# main.net
KiCad netlist of a schematic drawn in EAGLE
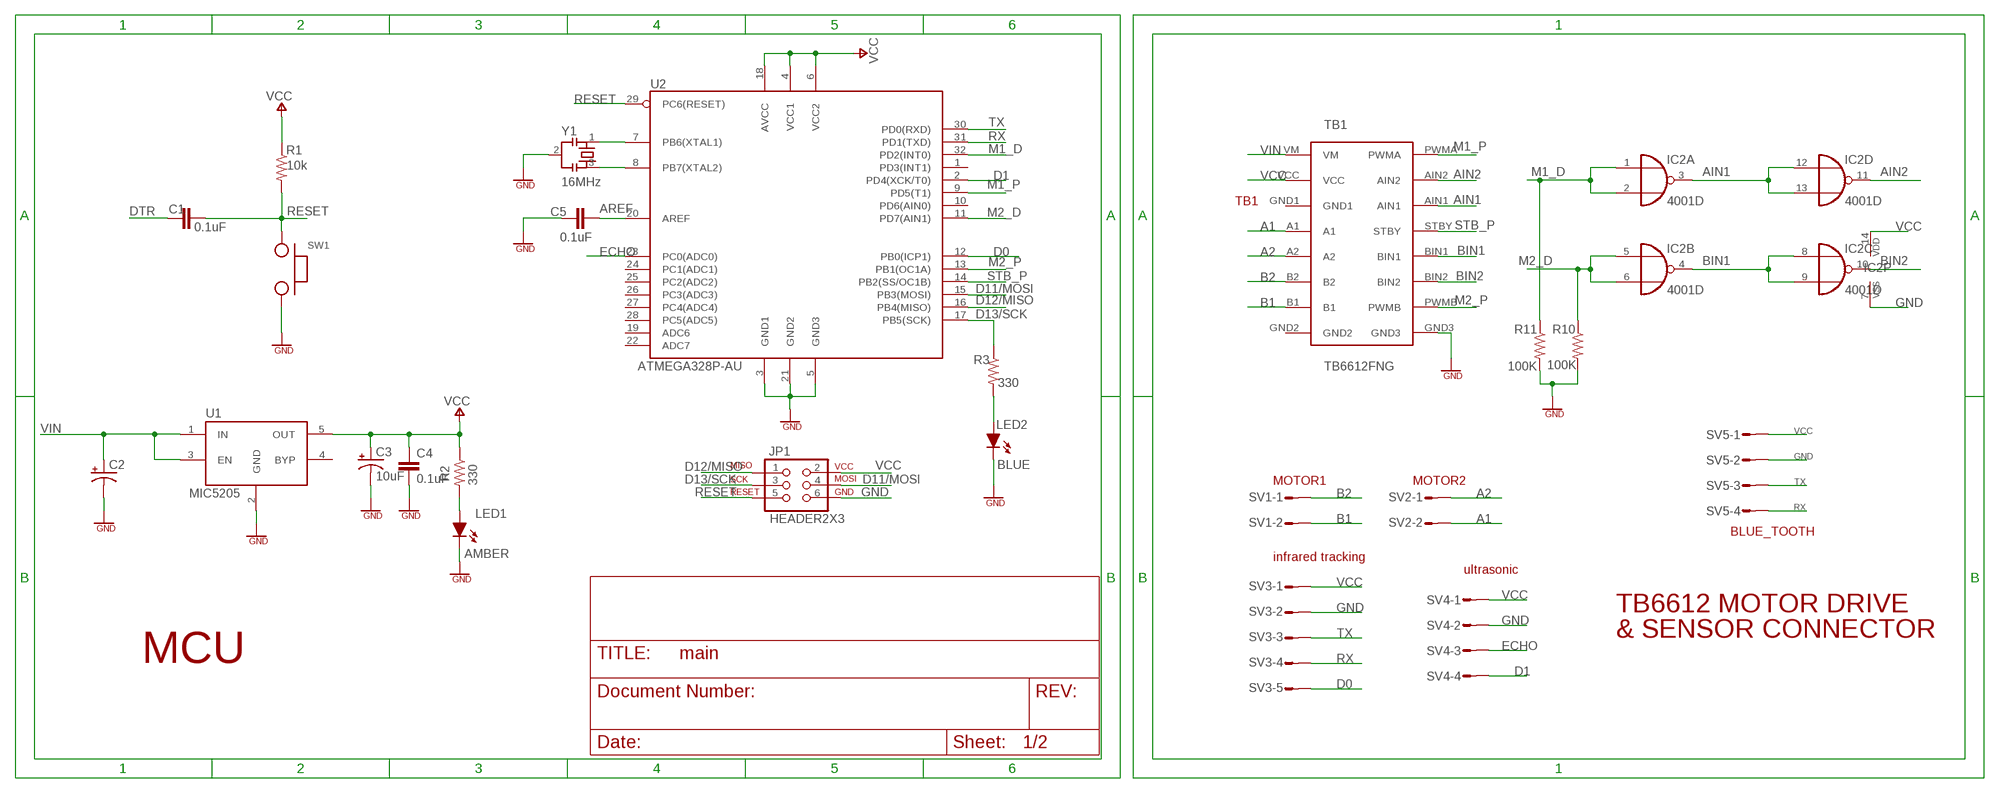
[diagram p0: schematic, sheet 1]
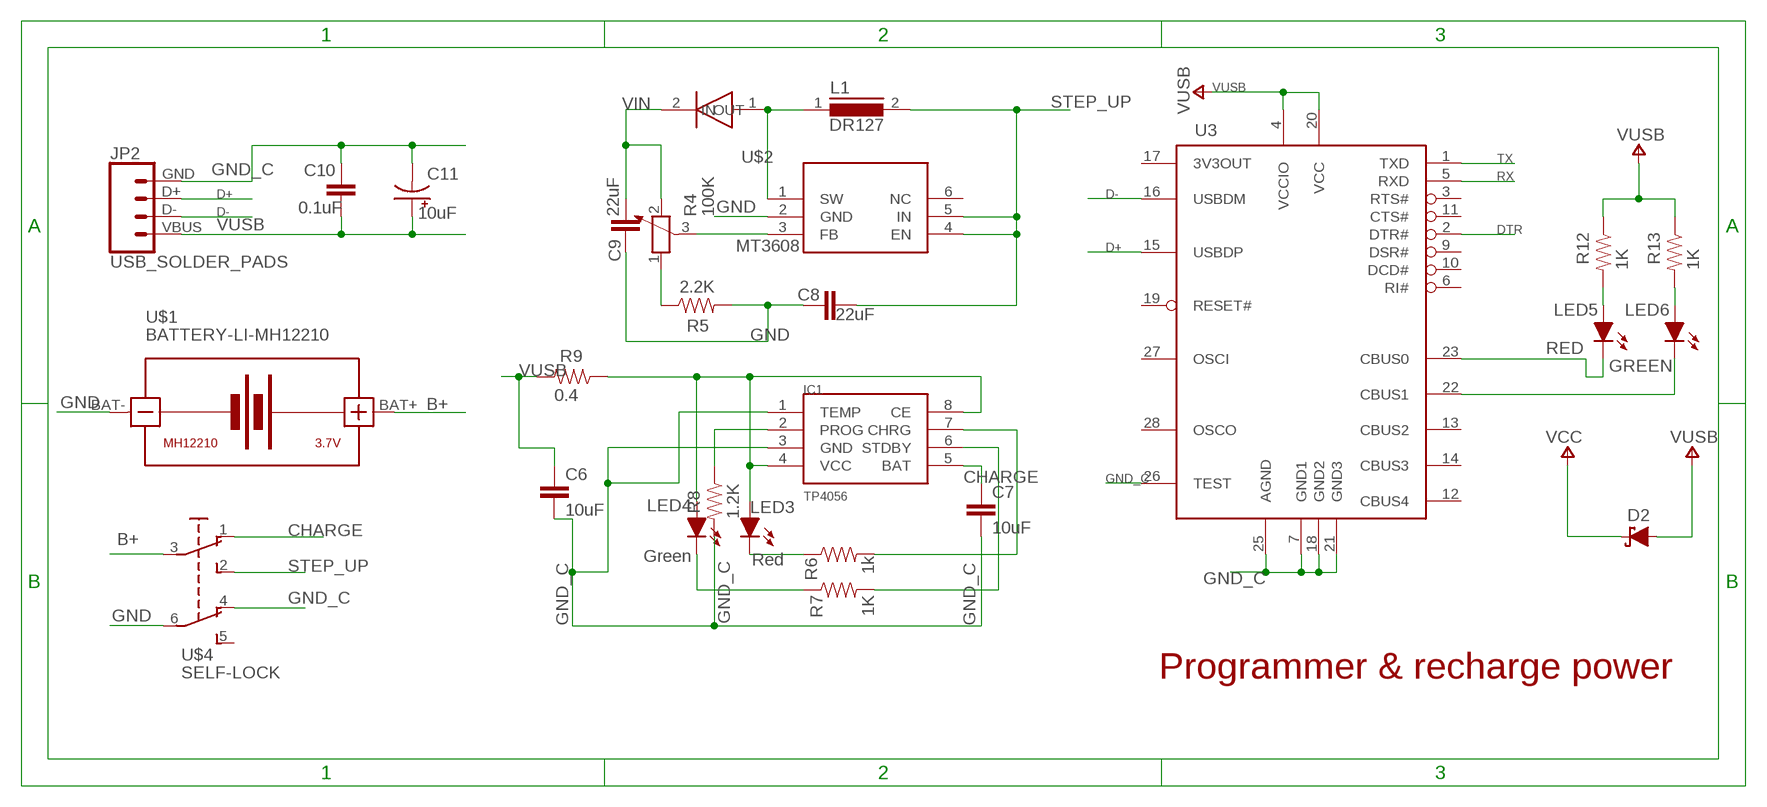
[diagram p1: schematic, sheet 2]

(export (version "E")
  (design (tool "Eeschema 10.0.6"))
  (components
    (comp (ref "C1")
      (value "0.1uF")
      (footprint "eagle-import:SMD0603")
      (libsource (lib "eagle-import") (part "CAP_0603"))
    )
    (comp (ref "C2")
      (value "CAP_TANT")
      (footprint "eagle-import:EIA3216")
      (libsource (lib "eagle-import") (part "CAP_TANT"))
    )
    (comp (ref "C3")
      (value "10uF")
      (footprint "eagle-import:EIA3216")
      (libsource (lib "eagle-import") (part "CAP_TANT"))
    )
    (comp (ref "C4")
      (value "0.1uF")
      (footprint "eagle-import:SMD0603")
      (libsource (lib "eagle-import") (part "CAP_0603"))
    )
    (comp (ref "C5")
      (value "0.1uF")
      (footprint "eagle-import:SMD0603")
      (libsource (lib "eagle-import") (part "CAP_0603"))
    )
    (comp (ref "IC2")
      (value "4001D")
      (footprint "eagle-import:SO14")
      (libsource (lib "eagle-import") (part "4001D"))
    )
    (comp (ref "JP1")
      (value "HEADER2X3")
      (footprint "eagle-import:2X3")
      (libsource (lib "eagle-import") (part "HEADER2X3"))
    )
    (comp (ref "LED1")
      (value "AMBER")
      (footprint "eagle-import:LED_0603")
      (libsource (lib "eagle-import") (part "LED_0603"))
    )
    (comp (ref "LED2")
      (value "BLUE")
      (footprint "eagle-import:LED_0805")
      (libsource (lib "eagle-import") (part "LED_0805"))
    )
    (comp (ref "R1")
      (value "10k")
      (footprint "eagle-import:SMD0603")
      (libsource (lib "eagle-import") (part "RES_0603"))
    )
    (comp (ref "R2")
      (value "330")
      (footprint "eagle-import:SMD0603")
      (libsource (lib "eagle-import") (part "RES_0603"))
    )
    (comp (ref "R3")
      (value "330")
      (footprint "eagle-import:SMD0603")
      (libsource (lib "eagle-import") (part "RES_0603"))
    )
    (comp (ref "R10")
      (value "100K")
      (footprint "eagle-import:SMD0603")
      (libsource (lib "eagle-import") (part "RES_0603"))
    )
    (comp (ref "R11")
      (value "100K")
      (footprint "eagle-import:SMD0603")
      (libsource (lib "eagle-import") (part "RES_0603"))
    )
    (comp (ref "SV1")
      (value "L02P")
      (footprint "eagle-import:L02P")
      (libsource (lib "eagle-import") (part "L02P"))
    )
    (comp (ref "SV2")
      (value "L02P")
      (footprint "eagle-import:L02P")
      (libsource (lib "eagle-import") (part "L02P"))
    )
    (comp (ref "SV3")
      (value "L05P")
      (footprint "eagle-import:L05P")
      (libsource (lib "eagle-import") (part "L05P"))
    )
    (comp (ref "SV4")
      (value "MT6-4")
      (footprint "eagle-import:MT6-4")
      (libsource (lib "eagle-import") (part "MT6-4"))
    )
    (comp (ref "SV5")
      (value "MT6-4")
      (footprint "eagle-import:MT6-4")
      (libsource (lib "eagle-import") (part "MT6-4"))
    )
    (comp (ref "SW1")
      (value "SWITCH")
      (footprint "eagle-import:SWITCH-SPST")
      (libsource (lib "eagle-import") (part "SWITCH"))
    )
    (comp (ref "TB1")
      (value "TB6612FNG")
      (footprint "eagle-import:TB6612FNG")
      (libsource (lib "eagle-import") (part "TB6612FNG"))
    )
    (comp (ref "U1")
      (value "MIC5205")
      (footprint "eagle-import:SOT23-5")
      (libsource (lib "eagle-import") (part "MIC5205"))
    )
    (comp (ref "U2")
      (value "ATMEGA328P-AU")
      (footprint "eagle-import:TQFP32")
      (libsource (lib "eagle-import") (part "ATMEGA328P-AU"))
    )
    (comp (ref "Y1")
      (value "16MHz")
      (footprint "eagle-import:CSTCE")
      (libsource (lib "eagle-import") (part "CSTCE"))
    )
    (comp (ref "C6")
      (value "10uF")
      (footprint "eagle-import:SMD0805")
      (libsource (lib "eagle-import") (part "CAP_0805"))
    )
    (comp (ref "C7")
      (value "10uF")
      (footprint "eagle-import:SMD0805")
      (libsource (lib "eagle-import") (part "CAP_0805"))
    )
    (comp (ref "C8")
      (value "22uF")
      (footprint "eagle-import:SMD0805")
      (libsource (lib "eagle-import") (part "CAP_0805"))
    )
    (comp (ref "C9")
      (value "22uF")
      (footprint "eagle-import:SMD0805")
      (libsource (lib "eagle-import") (part "CAP_0805"))
    )
    (comp (ref "C10")
      (value "0.1uF")
      (footprint "eagle-import:SMD0603")
      (libsource (lib "eagle-import") (part "CAP_0603"))
    )
    (comp (ref "C11")
      (value "10uF")
      (footprint "eagle-import:EIA3216")
      (libsource (lib "eagle-import") (part "CAP_TANT"))
    )
    (comp (ref "D2")
      (value "SCHOTTKY")
      (footprint "eagle-import:SOD123")
      (libsource (lib "eagle-import") (part "SCHOTTKY"))
    )
    (comp (ref "IC1")
      (value "TP4056")
      (footprint "eagle-import:SOP-8")
      (libsource (lib "eagle-import") (part "TP4056"))
    )
    (comp (ref "JP2")
      (value "USB_SOLDER_PADS")
      (footprint "eagle-import:USB-SOLDER-PADS")
      (libsource (lib "eagle-import") (part "USB_SOLDER_PADS"))
    )
    (comp (ref "L1")
      (value "DR127")
      (footprint "eagle-import:DR127")
      (libsource (lib "eagle-import") (part "DR127"))
    )
    (comp (ref "LED3")
      (value "Red")
      (footprint "eagle-import:LED_0603")
      (libsource (lib "eagle-import") (part "LED_0603"))
    )
    (comp (ref "LED4")
      (value "Green")
      (footprint "eagle-import:LED_0603")
      (libsource (lib "eagle-import") (part "LED_0603"))
    )
    (comp (ref "LED5")
      (value "RED")
      (footprint "eagle-import:LED_0603")
      (libsource (lib "eagle-import") (part "LED_0603"))
    )
    (comp (ref "LED6")
      (value "GREEN")
      (footprint "eagle-import:LED_0603")
      (libsource (lib "eagle-import") (part "LED_0603"))
    )
    (comp (ref "R4")
      (value "100K")
      (footprint "eagle-import:PT-10")
      (libsource (lib "eagle-import") (part "POTENTIOMETER_PT-10"))
    )
    (comp (ref "R5")
      (value "2.2K")
      (footprint "eagle-import:SMD0603")
      (libsource (lib "eagle-import") (part "RES_0603"))
    )
    (comp (ref "R6")
      (value "1k")
      (footprint "eagle-import:SMD0603")
      (libsource (lib "eagle-import") (part "RES_0603"))
    )
    (comp (ref "R7")
      (value "1K")
      (footprint "eagle-import:SMD0603")
      (libsource (lib "eagle-import") (part "RES_0603"))
    )
    (comp (ref "R8")
      (value "1.2K")
      (footprint "eagle-import:SMD0603")
      (libsource (lib "eagle-import") (part "RES_0603"))
    )
    (comp (ref "R9")
      (value "0.4")
      (footprint "eagle-import:SMD0805")
      (libsource (lib "eagle-import") (part "RES_0805"))
    )
    (comp (ref "R12")
      (value "1K")
      (footprint "eagle-import:SMD0603")
      (libsource (lib "eagle-import") (part "RES_0603"))
    )
    (comp (ref "R13")
      (value "1K")
      (footprint "eagle-import:SMD0603")
      (libsource (lib "eagle-import") (part "RES_0603"))
    )
    (comp (ref "U$1")
      (value "BATTERY-LI-MH12210")
      (footprint "eagle-import:BATTERY-LI-MH12210")
      (libsource (lib "eagle-import") (part "BATTERY-LI-MH12210"))
    )
    (comp (ref "U$2")
      (value "MT3608")
      (footprint "eagle-import:SOT23-6")
      (libsource (lib "eagle-import") (part "MT3608"))
    )
    (comp (ref "U$3")
      (value "SMA-SS34")
      (footprint "eagle-import:SMA-SS34")
      (libsource (lib "eagle-import") (part "SMA-SS34"))
    )
    (comp (ref "U$4")
      (value "SELF-LOCK")
      (footprint "eagle-import:SELF-LOCK")
      (libsource (lib "eagle-import") (part "SELF-LOCK"))
    )
    (comp (ref "U3")
      (value "FT232RL")
      (footprint "eagle-import:SSOP28DB")
      (libsource (lib "eagle-import") (part "FT232RL"))
    )
  )
  (nets
    (net (code "1") (name "A1") (class "Default")
      (node (ref "SV2") (pin "2") (pinfunction "S_2") (pintype "passive"))
      (node (ref "TB1") (pin "A1") (pinfunction "A1_A1") (pintype "bidirectional"))
    )
    (net (code "2") (name "A2") (class "Default")
      (node (ref "SV2") (pin "1") (pinfunction "S_1") (pintype "passive"))
      (node (ref "TB1") (pin "A2") (pinfunction "A2_A2") (pintype "bidirectional"))
    )
    (net (code "3") (name "AIN1") (class "Default")
      (node (ref "IC2") (pin "12") (pinfunction "I0_12") (pintype "input"))
      (node (ref "IC2") (pin "13") (pinfunction "I1_13") (pintype "input"))
      (node (ref "IC2") (pin "3") (pinfunction "O_3") (pintype "output"))
      (node (ref "TB1") (pin "AIN1") (pinfunction "AIN1_AIN1") (pintype "bidirectional"))
    )
    (net (code "4") (name "AIN2") (class "Default")
      (node (ref "IC2") (pin "11") (pinfunction "O_11") (pintype "output"))
      (node (ref "TB1") (pin "AIN2") (pinfunction "AIN2_AIN2") (pintype "bidirectional"))
    )
    (net (code "5") (name "AREF") (class "Default")
      (node (ref "C5") (pin "2") (pinfunction "2_2") (pintype "passive"))
      (node (ref "U2") (pin "20") (pinfunction "AREF_20") (pintype "bidirectional"))
    )
    (net (code "6") (name "B+") (class "Default")
      (node (ref "U$1") (pin "BAT+") (pinfunction "BAT+_BAT+") (pintype "power_in"))
      (node (ref "U$4") (pin "3") (pinfunction "3_3") (pintype "passive"))
    )
    (net (code "7") (name "B1") (class "Default")
      (node (ref "SV1") (pin "2") (pinfunction "S_2") (pintype "passive"))
      (node (ref "TB1") (pin "B1") (pinfunction "B1_B1") (pintype "bidirectional"))
    )
    (net (code "8") (name "B2") (class "Default")
      (node (ref "SV1") (pin "1") (pinfunction "S_1") (pintype "passive"))
      (node (ref "TB1") (pin "B2") (pinfunction "B2_B2") (pintype "bidirectional"))
    )
    (net (code "9") (name "BIN1") (class "Default")
      (node (ref "IC2") (pin "4") (pinfunction "O_4") (pintype "output"))
      (node (ref "IC2") (pin "8") (pinfunction "I0_8") (pintype "input"))
      (node (ref "IC2") (pin "9") (pinfunction "I1_9") (pintype "input"))
      (node (ref "TB1") (pin "BIN1") (pinfunction "BIN1_BIN1") (pintype "bidirectional"))
    )
    (net (code "10") (name "BIN2") (class "Default")
      (node (ref "IC2") (pin "10") (pinfunction "O_10") (pintype "output"))
      (node (ref "TB1") (pin "BIN2") (pinfunction "BIN2_BIN2") (pintype "bidirectional"))
    )
    (net (code "11") (name "CHARGE") (class "Default")
      (node (ref "C7") (pin "1") (pinfunction "1_1") (pintype "passive"))
      (node (ref "IC1") (pin "5") (pinfunction "BAT_5") (pintype "bidirectional"))
      (node (ref "U$4") (pin "1") (pinfunction "1_1") (pintype "passive"))
    )
    (net (code "12") (name "D+") (class "Default")
      (node (ref "JP2") (pin "D+") (pinfunction "3_D+") (pintype "passive"))
      (node (ref "U3") (pin "15") (pinfunction "USBDP_15") (pintype "bidirectional"))
    )
    (net (code "13") (name "D-") (class "Default")
      (node (ref "JP2") (pin "D-") (pinfunction "2_D-") (pintype "passive"))
      (node (ref "U3") (pin "16") (pinfunction "USBDM_16") (pintype "bidirectional"))
    )
    (net (code "14") (name "D0") (class "Default")
      (node (ref "SV3") (pin "5") (pinfunction "S_5") (pintype "passive"))
      (node (ref "U2") (pin "12") (pinfunction "PB0(ICP1)_12") (pintype "bidirectional"))
    )
    (net (code "15") (name "D1") (class "Default")
      (node (ref "SV4") (pin "4") (pinfunction "S_4") (pintype "passive"))
      (node (ref "U2") (pin "2") (pinfunction "PD4(XCK/T0)_2") (pintype "bidirectional"))
    )
    (net (code "16") (name "D11{slash}MOSI") (class "Default")
      (node (ref "JP1") (pin "4") (pinfunction "4_4") (pintype "passive"))
      (node (ref "U2") (pin "15") (pinfunction "PB3(MOSI)_15") (pintype "bidirectional"))
    )
    (net (code "17") (name "D12{slash}MISO") (class "Default")
      (node (ref "JP1") (pin "1") (pinfunction "1_1") (pintype "passive"))
      (node (ref "U2") (pin "16") (pinfunction "PB4(MISO)_16") (pintype "bidirectional"))
    )
    (net (code "18") (name "D13{slash}SCK") (class "Default")
      (node (ref "JP1") (pin "3") (pinfunction "3_3") (pintype "passive"))
      (node (ref "R3") (pin "1") (pinfunction "1_1") (pintype "passive"))
      (node (ref "U2") (pin "17") (pinfunction "PB5(SCK)_17") (pintype "bidirectional"))
    )
    (net (code "19") (name "DTR") (class "Default")
      (node (ref "C1") (pin "2") (pinfunction "2_2") (pintype "passive"))
      (node (ref "U3") (pin "2") (pinfunction "DTR#_2") (pintype "output"))
    )
    (net (code "20") (name "ECHO") (class "Default")
      (node (ref "SV4") (pin "3") (pinfunction "S_3") (pintype "passive"))
      (node (ref "U2") (pin "23") (pinfunction "PC0(ADC0)_23") (pintype "bidirectional"))
    )
    (net (code "21") (name "GND") (class "Default")
      (node (ref "C2") (pin "C") (pinfunction "-_C") (pintype "passive"))
      (node (ref "C3") (pin "C") (pinfunction "-_C") (pintype "passive"))
      (node (ref "C4") (pin "2") (pinfunction "2_2") (pintype "passive"))
      (node (ref "C5") (pin "1") (pinfunction "1_1") (pintype "passive"))
      (node (ref "C8") (pin "1") (pinfunction "1_1") (pintype "passive"))
      (node (ref "C9") (pin "1") (pinfunction "1_1") (pintype "passive"))
      (node (ref "IC2") (pin "7") (pinfunction "VSS_7") (pintype "power_in"))
      (node (ref "JP1") (pin "6") (pinfunction "6_6") (pintype "passive"))
      (node (ref "LED1") (pin "C") (pinfunction "C_C") (pintype "passive"))
      (node (ref "LED2") (pin "C") (pinfunction "C_C") (pintype "passive"))
      (node (ref "R10") (pin "2") (pinfunction "2_2") (pintype "passive"))
      (node (ref "R11") (pin "2") (pinfunction "2_2") (pintype "passive"))
      (node (ref "R5") (pin "2") (pinfunction "2_2") (pintype "passive"))
      (node (ref "SV3") (pin "2") (pinfunction "S_2") (pintype "passive"))
      (node (ref "SV4") (pin "2") (pinfunction "S_2") (pintype "passive"))
      (node (ref "SV5") (pin "2") (pinfunction "S_2") (pintype "passive"))
      (node (ref "SW1") (pin "2") (pinfunction "2_2") (pintype "bidirectional"))
      (node (ref "TB1") (pin "GND3") (pinfunction "GND3_GND3") (pintype "bidirectional"))
      (node (ref "U$1") (pin "BAT-") (pinfunction "BAT-_BAT-") (pintype "power_in"))
      (node (ref "U$2") (pin "2") (pinfunction "GND_2") (pintype "power_in"))
      (node (ref "U$4") (pin "6") (pinfunction "6_6") (pintype "passive"))
      (node (ref "U1") (pin "2") (pinfunction "GND_2") (pintype "bidirectional"))
      (node (ref "U2") (pin "21") (pinfunction "GND2_21") (pintype "bidirectional"))
      (node (ref "U2") (pin "3") (pinfunction "GND1_3") (pintype "bidirectional"))
      (node (ref "U2") (pin "5") (pinfunction "GND3_5") (pintype "bidirectional"))
      (node (ref "Y1") (pin "2") (pinfunction "2_2") (pintype "passive"))
    )
    (net (code "22") (name "GND_C") (class "Default")
      (node (ref "C10") (pin "1") (pinfunction "1_1") (pintype "passive"))
      (node (ref "C11") (pin "C") (pinfunction "-_C") (pintype "passive"))
      (node (ref "C6") (pin "2") (pinfunction "2_2") (pintype "passive"))
      (node (ref "C7") (pin "2") (pinfunction "2_2") (pintype "passive"))
      (node (ref "IC1") (pin "1") (pinfunction "TEMP_1") (pintype "bidirectional"))
      (node (ref "IC1") (pin "3") (pinfunction "GND_3") (pintype "bidirectional"))
      (node (ref "JP2") (pin "GND") (pinfunction "4_GND") (pintype "passive"))
      (node (ref "R8") (pin "2") (pinfunction "2_2") (pintype "passive"))
      (node (ref "U$4") (pin "4") (pinfunction "4_4") (pintype "passive"))
      (node (ref "U3") (pin "18") (pinfunction "GND2_18") (pintype "power_in"))
      (node (ref "U3") (pin "21") (pinfunction "GND3_21") (pintype "power_in"))
      (node (ref "U3") (pin "25") (pinfunction "AGND_25") (pintype "power_in"))
      (node (ref "U3") (pin "26") (pinfunction "TEST_26") (pintype "input"))
      (node (ref "U3") (pin "7") (pinfunction "GND1_7") (pintype "power_in"))
    )
    (net (code "23") (name "M1_D") (class "Default")
      (node (ref "IC2") (pin "1") (pinfunction "I0_1") (pintype "input"))
      (node (ref "IC2") (pin "2") (pinfunction "I1_2") (pintype "input"))
      (node (ref "R11") (pin "1") (pinfunction "1_1") (pintype "passive"))
      (node (ref "U2") (pin "32") (pinfunction "PD2(INT0)_32") (pintype "bidirectional"))
    )
    (net (code "24") (name "M1_P") (class "Default")
      (node (ref "TB1") (pin "PWMA") (pinfunction "PWMA_PWMA") (pintype "bidirectional"))
      (node (ref "U2") (pin "9") (pinfunction "PD5(T1)_9") (pintype "bidirectional"))
    )
    (net (code "25") (name "M2_D") (class "Default")
      (node (ref "IC2") (pin "5") (pinfunction "I0_5") (pintype "input"))
      (node (ref "IC2") (pin "6") (pinfunction "I1_6") (pintype "input"))
      (node (ref "R10") (pin "1") (pinfunction "1_1") (pintype "passive"))
      (node (ref "U2") (pin "11") (pinfunction "PD7(AIN1)_11") (pintype "bidirectional"))
    )
    (net (code "26") (name "M2_P") (class "Default")
      (node (ref "TB1") (pin "PWMB") (pinfunction "PWMB_PWMB") (pintype "bidirectional"))
      (node (ref "U2") (pin "13") (pinfunction "PB1(OC1A)_13") (pintype "bidirectional"))
    )
    (net (code "27") (name "Net-(IC1-CE)") (class "Default")
      (node (ref "IC1") (pin "4") (pinfunction "VCC_4") (pintype "bidirectional"))
      (node (ref "IC1") (pin "8") (pinfunction "CE_8") (pintype "bidirectional"))
      (node (ref "LED3") (pin "A") (pinfunction "A_A") (pintype "passive"))
      (node (ref "LED4") (pin "A") (pinfunction "A_A") (pintype "passive"))
      (node (ref "R9") (pin "1") (pinfunction "1_1") (pintype "passive"))
    )
    (net (code "28") (name "Net-(IC1-CHRG)") (class "Default")
      (node (ref "IC1") (pin "7") (pinfunction "CHRG_7") (pintype "bidirectional"))
      (node (ref "R6") (pin "2") (pinfunction "2_2") (pintype "passive"))
    )
    (net (code "29") (name "Net-(IC1-PROG)") (class "Default")
      (node (ref "IC1") (pin "2") (pinfunction "PROG_2") (pintype "bidirectional"))
      (node (ref "R8") (pin "1") (pinfunction "1_1") (pintype "passive"))
    )
    (net (code "30") (name "Net-(IC1-STDBY)") (class "Default")
      (node (ref "IC1") (pin "6") (pinfunction "STDBY_6") (pintype "bidirectional"))
      (node (ref "R7") (pin "2") (pinfunction "2_2") (pintype "passive"))
    )
    (net (code "31") (name "Net-(LED1-PadA)") (class "Default")
      (node (ref "LED1") (pin "A") (pinfunction "A_A") (pintype "passive"))
      (node (ref "R2") (pin "2") (pinfunction "2_2") (pintype "passive"))
    )
    (net (code "32") (name "Net-(LED2-PadA)") (class "Default")
      (node (ref "LED2") (pin "A") (pinfunction "A_A") (pintype "passive"))
      (node (ref "R3") (pin "2") (pinfunction "2_2") (pintype "passive"))
    )
    (net (code "33") (name "Net-(LED3-PadC)") (class "Default")
      (node (ref "LED3") (pin "C") (pinfunction "C_C") (pintype "passive"))
      (node (ref "R6") (pin "1") (pinfunction "1_1") (pintype "passive"))
    )
    (net (code "34") (name "Net-(LED4-PadC)") (class "Default")
      (node (ref "LED4") (pin "C") (pinfunction "C_C") (pintype "passive"))
      (node (ref "R7") (pin "1") (pinfunction "1_1") (pintype "passive"))
    )
    (net (code "35") (name "Net-(LED5-PadA)") (class "Default")
      (node (ref "LED5") (pin "A") (pinfunction "A_A") (pintype "passive"))
      (node (ref "R12") (pin "2") (pinfunction "2_2") (pintype "passive"))
    )
    (net (code "36") (name "Net-(LED6-PadA)") (class "Default")
      (node (ref "LED6") (pin "A") (pinfunction "A_A") (pintype "passive"))
      (node (ref "R13") (pin "2") (pinfunction "2_2") (pintype "passive"))
    )
    (net (code "37") (name "Net-(R4-Pad1)") (class "Default")
      (node (ref "R4") (pin "1") (pinfunction "1_1") (pintype "passive"))
      (node (ref "R5") (pin "1") (pinfunction "1_1") (pintype "passive"))
    )
    (net (code "38") (name "Net-(U$2-FB)") (class "Default")
      (node (ref "R4") (pin "3") (pinfunction "3_3") (pintype "passive"))
      (node (ref "U$2") (pin "3") (pinfunction "FB_3") (pintype "input"))
    )
    (net (code "39") (name "Net-(U$2-SW)") (class "Default")
      (node (ref "L1") (pin "1") (pinfunction "1_1") (pintype "passive"))
      (node (ref "U$2") (pin "1") (pinfunction "SW_1") (pintype "output"))
      (node (ref "U$3") (pin "1") (pinfunction "IN_1") (pintype "input"))
    )
    (net (code "40") (name "Net-(U2-PB6(XTAL1))") (class "Default")
      (node (ref "U2") (pin "7") (pinfunction "PB6(XTAL1)_7") (pintype "bidirectional"))
      (node (ref "Y1") (pin "1") (pinfunction "1_1") (pintype "passive"))
    )
    (net (code "41") (name "Net-(U2-PB7(XTAL2))") (class "Default")
      (node (ref "U2") (pin "8") (pinfunction "PB7(XTAL2)_8") (pintype "bidirectional"))
      (node (ref "Y1") (pin "3") (pinfunction "3_3") (pintype "passive"))
    )
    (net (code "42") (name "Net-(U3-CBUS0)") (class "Default")
      (node (ref "LED5") (pin "C") (pinfunction "C_C") (pintype "passive"))
      (node (ref "U3") (pin "23") (pinfunction "CBUS0_23") (pintype "bidirectional"))
    )
    (net (code "43") (name "Net-(U3-CBUS1)") (class "Default")
      (node (ref "LED6") (pin "C") (pinfunction "C_C") (pintype "passive"))
      (node (ref "U3") (pin "22") (pinfunction "CBUS1_22") (pintype "bidirectional"))
    )
    (net (code "44") (name "RESET") (class "Default")
      (node (ref "C1") (pin "1") (pinfunction "1_1") (pintype "passive"))
      (node (ref "JP1") (pin "5") (pinfunction "5_5") (pintype "passive"))
      (node (ref "R1") (pin "2") (pinfunction "2_2") (pintype "passive"))
      (node (ref "SW1") (pin "1") (pinfunction "1_1") (pintype "bidirectional"))
      (node (ref "U2") (pin "29") (pinfunction "PC6(RESET)_29") (pintype "bidirectional"))
    )
    (net (code "45") (name "RX") (class "Default")
      (node (ref "SV3") (pin "4") (pinfunction "S_4") (pintype "passive"))
      (node (ref "SV5") (pin "4") (pinfunction "S_4") (pintype "passive"))
      (node (ref "U2") (pin "31") (pinfunction "PD1(TXD)_31") (pintype "bidirectional"))
      (node (ref "U3") (pin "5") (pinfunction "RXD_5") (pintype "input"))
    )
    (net (code "46") (name "STB_P") (class "Default")
      (node (ref "TB1") (pin "STBY") (pinfunction "STBY_STBY") (pintype "bidirectional"))
      (node (ref "U2") (pin "14") (pinfunction "PB2(SS/OC1B)_14") (pintype "bidirectional"))
    )
    (net (code "47") (name "STEP_UP") (class "Default")
      (node (ref "C8") (pin "2") (pinfunction "2_2") (pintype "passive"))
      (node (ref "L1") (pin "2") (pinfunction "2_2") (pintype "passive"))
      (node (ref "U$2") (pin "4") (pinfunction "EN_4") (pintype "input"))
      (node (ref "U$2") (pin "5") (pinfunction "IN_5") (pintype "power_in"))
      (node (ref "U$4") (pin "2") (pinfunction "2_2") (pintype "passive"))
    )
    (net (code "48") (name "TX") (class "Default")
      (node (ref "SV3") (pin "3") (pinfunction "S_3") (pintype "passive"))
      (node (ref "SV5") (pin "3") (pinfunction "S_3") (pintype "passive"))
      (node (ref "U2") (pin "30") (pinfunction "PD0(RXD)_30") (pintype "bidirectional"))
      (node (ref "U3") (pin "1") (pinfunction "TXD_1") (pintype "output"))
    )
    (net (code "49") (name "VCC") (class "Default")
      (node (ref "C3") (pin "A") (pinfunction "+_A") (pintype "passive"))
      (node (ref "C4") (pin "1") (pinfunction "1_1") (pintype "passive"))
      (node (ref "D2") (pin "1") (pinfunction "C_1") (pintype "passive"))
      (node (ref "IC2") (pin "14") (pinfunction "VDD_14") (pintype "power_in"))
      (node (ref "JP1") (pin "2") (pinfunction "2_2") (pintype "passive"))
      (node (ref "R1") (pin "1") (pinfunction "1_1") (pintype "passive"))
      (node (ref "R2") (pin "1") (pinfunction "1_1") (pintype "passive"))
      (node (ref "SV3") (pin "1") (pinfunction "S_1") (pintype "passive"))
      (node (ref "SV4") (pin "1") (pinfunction "S_1") (pintype "passive"))
      (node (ref "SV5") (pin "1") (pinfunction "S_1") (pintype "passive"))
      (node (ref "TB1") (pin "VCC") (pinfunction "VCC_VCC") (pintype "bidirectional"))
      (node (ref "U1") (pin "5") (pinfunction "OUT_5") (pintype "bidirectional"))
      (node (ref "U2") (pin "18") (pinfunction "AVCC_18") (pintype "bidirectional"))
      (node (ref "U2") (pin "4") (pinfunction "VCC1_4") (pintype "bidirectional"))
      (node (ref "U2") (pin "6") (pinfunction "VCC2_6") (pintype "bidirectional"))
    )
    (net (code "50") (name "VIN") (class "Default")
      (node (ref "C2") (pin "A") (pinfunction "+_A") (pintype "passive"))
      (node (ref "C9") (pin "2") (pinfunction "2_2") (pintype "passive"))
      (node (ref "R4") (pin "2") (pinfunction "2_2") (pintype "passive"))
      (node (ref "TB1") (pin "VM") (pinfunction "VM_VM") (pintype "bidirectional"))
      (node (ref "U$3") (pin "2") (pinfunction "OUT_2") (pintype "bidirectional"))
      (node (ref "U1") (pin "1") (pinfunction "IN_1") (pintype "bidirectional"))
      (node (ref "U1") (pin "3") (pinfunction "EN_3") (pintype "bidirectional"))
    )
    (net (code "51") (name "VUSB") (class "Default")
      (node (ref "C10") (pin "2") (pinfunction "2_2") (pintype "passive"))
      (node (ref "C11") (pin "A") (pinfunction "+_A") (pintype "passive"))
      (node (ref "C6") (pin "1") (pinfunction "1_1") (pintype "passive"))
      (node (ref "D2") (pin "2") (pinfunction "A_2") (pintype "passive"))
      (node (ref "JP2") (pin "VBUS") (pinfunction "1_VBUS") (pintype "passive"))
      (node (ref "R12") (pin "1") (pinfunction "1_1") (pintype "passive"))
      (node (ref "R13") (pin "1") (pinfunction "1_1") (pintype "passive"))
      (node (ref "R9") (pin "2") (pinfunction "2_2") (pintype "passive"))
      (node (ref "U3") (pin "20") (pinfunction "VCC_20") (pintype "power_in"))
      (node (ref "U3") (pin "4") (pinfunction "VCCIO_4") (pintype "power_in"))
    )
    (net (code "52") (name "unconnected-(TB1-PadGND1)") (class "Default")
      (node (ref "TB1") (pin "GND1") (pinfunction "GND1_GND1") (pintype "bidirectional"))
    )
    (net (code "53") (name "unconnected-(TB1-PadGND2)") (class "Default")
      (node (ref "TB1") (pin "GND2") (pinfunction "GND2_GND2") (pintype "bidirectional"))
    )
    (net (code "54") (name "unconnected-(U$2-NC-Pad6)") (class "Default")
      (node (ref "U$2") (pin "6") (pinfunction "NC_6") (pintype "no_connect"))
    )
    (net (code "55") (name "unconnected-(U$4-Pad5)") (class "Default")
      (node (ref "U$4") (pin "5") (pinfunction "5_5") (pintype "passive"))
    )
    (net (code "56") (name "unconnected-(U1-BYP-Pad4)") (class "Default")
      (node (ref "U1") (pin "4") (pinfunction "BYP_4") (pintype "passive"))
    )
    (net (code "57") (name "unconnected-(U2-ADC6-Pad19)") (class "Default")
      (node (ref "U2") (pin "19") (pinfunction "ADC6_19") (pintype "bidirectional"))
    )
    (net (code "58") (name "unconnected-(U2-ADC7-Pad22)") (class "Default")
      (node (ref "U2") (pin "22") (pinfunction "ADC7_22") (pintype "bidirectional"))
    )
    (net (code "59") (name "unconnected-(U2-PC1(ADC1)-Pad24)") (class "Default")
      (node (ref "U2") (pin "24") (pinfunction "PC1(ADC1)_24") (pintype "bidirectional"))
    )
    (net (code "60") (name "unconnected-(U2-PC2(ADC2)-Pad25)") (class "Default")
      (node (ref "U2") (pin "25") (pinfunction "PC2(ADC2)_25") (pintype "bidirectional"))
    )
    (net (code "61") (name "unconnected-(U2-PC3(ADC3)-Pad26)") (class "Default")
      (node (ref "U2") (pin "26") (pinfunction "PC3(ADC3)_26") (pintype "bidirectional"))
    )
    (net (code "62") (name "unconnected-(U2-PC4(ADC4)-Pad27)") (class "Default")
      (node (ref "U2") (pin "27") (pinfunction "PC4(ADC4)_27") (pintype "bidirectional"))
    )
    (net (code "63") (name "unconnected-(U2-PC5(ADC5)-Pad28)") (class "Default")
      (node (ref "U2") (pin "28") (pinfunction "PC5(ADC5)_28") (pintype "bidirectional"))
    )
    (net (code "64") (name "unconnected-(U2-PD3(INT1)-Pad1)") (class "Default")
      (node (ref "U2") (pin "1") (pinfunction "PD3(INT1)_1") (pintype "bidirectional"))
    )
    (net (code "65") (name "unconnected-(U2-PD6(AIN0)-Pad10)") (class "Default")
      (node (ref "U2") (pin "10") (pinfunction "PD6(AIN0)_10") (pintype "bidirectional"))
    )
    (net (code "66") (name "unconnected-(U3-3V3OUT-Pad17)") (class "Default")
      (node (ref "U3") (pin "17") (pinfunction "3V3OUT_17") (pintype "output"))
    )
    (net (code "67") (name "unconnected-(U3-CBUS2-Pad13)") (class "Default")
      (node (ref "U3") (pin "13") (pinfunction "CBUS2_13") (pintype "bidirectional"))
    )
    (net (code "68") (name "unconnected-(U3-CBUS3-Pad14)") (class "Default")
      (node (ref "U3") (pin "14") (pinfunction "CBUS3_14") (pintype "bidirectional"))
    )
    (net (code "69") (name "unconnected-(U3-CBUS4-Pad12)") (class "Default")
      (node (ref "U3") (pin "12") (pinfunction "CBUS4_12") (pintype "bidirectional"))
    )
    (net (code "70") (name "unconnected-(U3-CTS#-Pad11)") (class "Default")
      (node (ref "U3") (pin "11") (pinfunction "CTS#_11") (pintype "input"))
    )
    (net (code "71") (name "unconnected-(U3-DCD#-Pad10)") (class "Default")
      (node (ref "U3") (pin "10") (pinfunction "DCD#_10") (pintype "input"))
    )
    (net (code "72") (name "unconnected-(U3-DSR#-Pad9)") (class "Default")
      (node (ref "U3") (pin "9") (pinfunction "DSR#_9") (pintype "input"))
    )
    (net (code "73") (name "unconnected-(U3-OSCI-Pad27)") (class "Default")
      (node (ref "U3") (pin "27") (pinfunction "OSCI_27") (pintype "input"))
    )
    (net (code "74") (name "unconnected-(U3-OSCO-Pad28)") (class "Default")
      (node (ref "U3") (pin "28") (pinfunction "OSCO_28") (pintype "output"))
    )
    (net (code "75") (name "unconnected-(U3-RESET#-Pad19)") (class "Default")
      (node (ref "U3") (pin "19") (pinfunction "RESET#_19") (pintype "input"))
    )
    (net (code "76") (name "unconnected-(U3-RI#-Pad6)") (class "Default")
      (node (ref "U3") (pin "6") (pinfunction "RI#_6") (pintype "input"))
    )
    (net (code "77") (name "unconnected-(U3-RTS#-Pad3)") (class "Default")
      (node (ref "U3") (pin "3") (pinfunction "RTS#_3") (pintype "output"))
    )
  )
)
